# 05021002_Accelerometer.net
KiCad netlist of a schematic drawn in Altium Designer
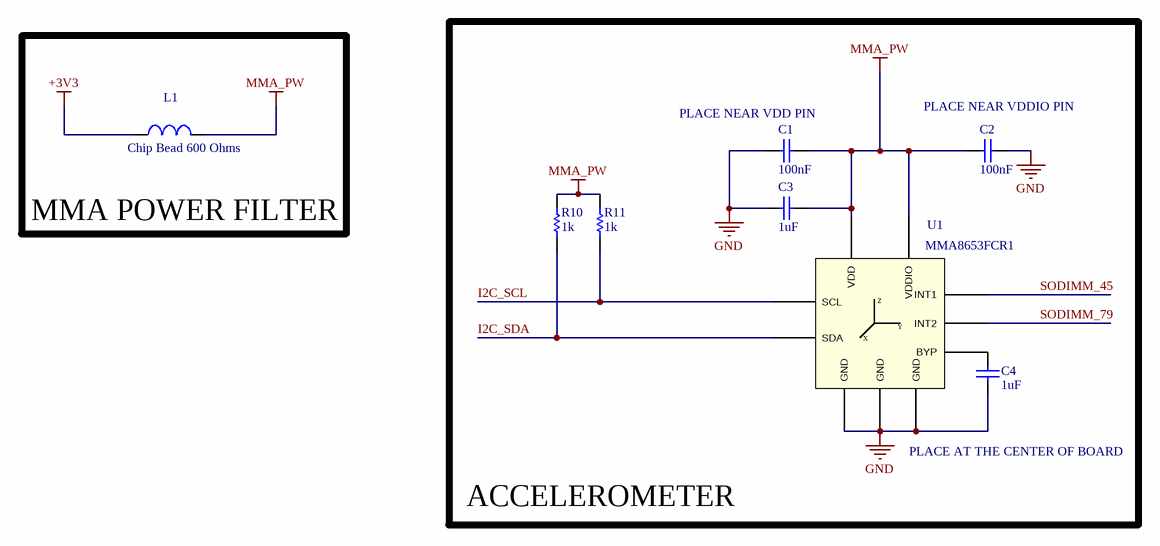
[diagram p0: 05021002_Accelerometer.SchDoc]

(export (version "E")
  (design (tool "Eeschema 10.0.6"))
  (components
    (comp (ref "C1")
      (value "100nF")
      (footprint "CAPC2012X135N")
      (description "Generic Capacitor")
      (libsource (lib "capacitor_smd_gen") (part "capacitor_gen"))
    )
    (comp (ref "C2")
      (value "100nF")
      (footprint "CAPC2012X135N")
      (description "Generic Capacitor")
      (libsource (lib "capacitor_smd_gen") (part "capacitor_gen"))
    )
    (comp (ref "C3")
      (value "1uF")
      (footprint "CAPC2012X135N")
      (description "Generic Capacitor")
      (libsource (lib "capacitor_smd_gen") (part "capacitor_gen"))
    )
    (comp (ref "C4")
      (value "1uF")
      (footprint "CAPC2012X135N")
      (description "Generic Capacitor")
      (libsource (lib "capacitor_smd_gen") (part "capacitor_gen"))
    )
    (comp (ref "L1")
      (value "Chip Bead 600 Ohms")
      (footprint "1608[0603]")
      (description "Wide Band Bead 600 Ohms - Rdc 0.45 mOhms 74279265")
      (libsource (lib "Eduardo") (part "L"))
    )
    (comp (ref "R10")
      (value "1k")
      (footprint "0805")
      (libsource (lib "resistor_smd_gen") (part "resistor_gen"))
    )
    (comp (ref "R11")
      (value "1k")
      (footprint "0805")
      (libsource (lib "resistor_smd_gen") (part "resistor_gen"))
    )
    (comp (ref "U1")
      (value "MMA8653FCR1")
      (footprint "MMA8653F")
      (libsource (lib "IPÊ_BOARD_LIBRARY") (part "MMA8653FCR1"))
    )
  )
  (nets
    (net (code "1") (name "+3V3") (class "Default")
      (node (ref "L1") (pin "1") (pinfunction "1_1") (pintype "passive"))
    )
    (net (code "2") (name "/I2C_SCL") (class "Default")
      (node (ref "R11") (pin "1") (pinfunction "1_1") (pintype "passive"))
      (node (ref "U1") (pin "2") (pinfunction "SCL_2") (pintype "passive"))
    )
    (net (code "3") (name "/I2C_SDA") (class "Default")
      (node (ref "R10") (pin "1") (pinfunction "1_1") (pintype "passive"))
      (node (ref "U1") (pin "10") (pinfunction "SDA_10") (pintype "passive"))
    )
    (net (code "4") (name "/SODIMM_45") (class "Default")
      (node (ref "U1") (pin "3") (pinfunction "INT1_3") (pintype "passive"))
    )
    (net (code "5") (name "/SODIMM_79") (class "Default")
      (node (ref "U1") (pin "5") (pinfunction "INT2_5") (pintype "passive"))
    )
    (net (code "6") (name "GND") (class "Default")
      (node (ref "C1") (pin "1") (pinfunction "1_1") (pintype "passive"))
      (node (ref "C2") (pin "2") (pinfunction "2_2") (pintype "passive"))
      (node (ref "C3") (pin "1") (pinfunction "1_1") (pintype "passive"))
      (node (ref "C4") (pin "1") (pinfunction "1_1") (pintype "passive"))
      (node (ref "U1") (pin "6") (pinfunction "GND_6") (pintype "passive"))
      (node (ref "U1") (pin "7") (pinfunction "GND_7") (pintype "passive"))
      (node (ref "U1") (pin "9") (pinfunction "GND_9") (pintype "passive"))
    )
    (net (code "7") (name "MMA_PW") (class "Default")
      (node (ref "C1") (pin "2") (pinfunction "2_2") (pintype "passive"))
      (node (ref "C2") (pin "1") (pinfunction "1_1") (pintype "passive"))
      (node (ref "C3") (pin "2") (pinfunction "2_2") (pintype "passive"))
      (node (ref "L1") (pin "2") (pinfunction "2_2") (pintype "passive"))
      (node (ref "R10") (pin "2") (pinfunction "2_2") (pintype "passive"))
      (node (ref "R11") (pin "2") (pinfunction "2_2") (pintype "passive"))
      (node (ref "U1") (pin "1") (pinfunction "VDD_1") (pintype "passive"))
      (node (ref "U1") (pin "8") (pinfunction "VDDIO_8") (pintype "passive"))
    )
    (net (code "8") (name "Net-(U1-BYP)") (class "Default")
      (node (ref "C4") (pin "2") (pinfunction "2_2") (pintype "passive"))
      (node (ref "U1") (pin "4") (pinfunction "BYP_4") (pintype "passive"))
    )
  )
)
